# SparkFun_Amplified-Mic.net
KiCad netlist of a schematic drawn in EAGLE
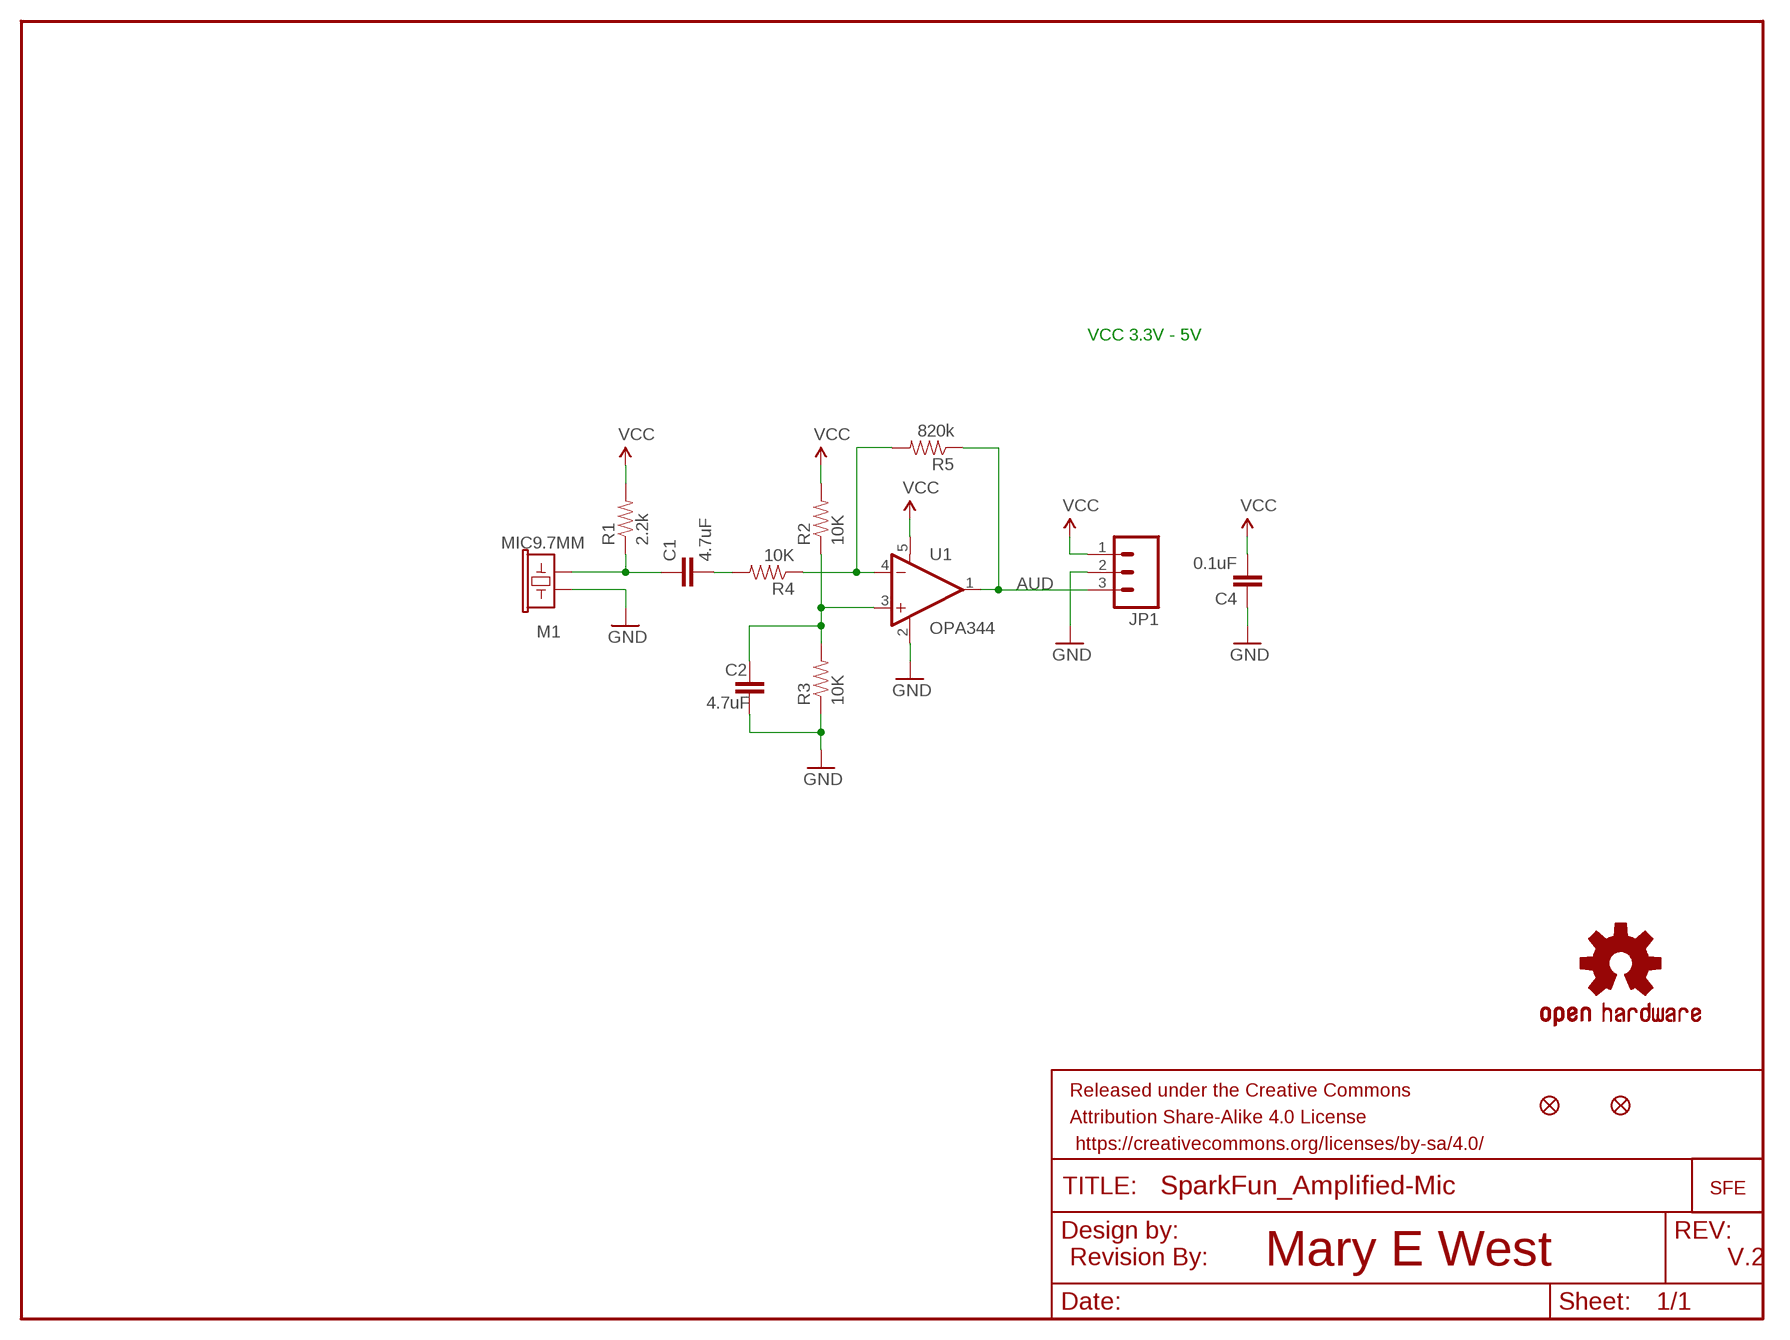
[diagram p0: schematic, sheet 1]

(export (version "E")
  (design (tool "Eeschema 10.0.6"))
  (components
    (comp (ref "C1")
      (value "4.7uF")
      (footprint "eagle-import:0603-CAP")
      (libsource (lib "eagle-import") (part "4.7UF-6.3V-10%(0603)0603"))
    )
    (comp (ref "C2")
      (value "4.7uF")
      (footprint "eagle-import:0603-CAP")
      (libsource (lib "eagle-import") (part "4.7UF-6.3V-10%(0603)0603"))
    )
    (comp (ref "C4")
      (value "0.1uF")
      (footprint "eagle-import:0603-CAP")
      (libsource (lib "eagle-import") (part "0.1UF-25V(+80/-20%)(0603)"))
    )
    (comp (ref "FRAME1")
      (value "FRAME-LETTER")
      (footprint "eagle-import:CREATIVE_COMMONS")
      (libsource (lib "eagle-import") (part "FRAME-LETTER"))
    )
    (comp (ref "JP1")
      (value "M03PTH")
      (footprint "eagle-import:1X03")
      (libsource (lib "eagle-import") (part "M03PTH"))
    )
    (comp (ref "JP2")
      (value "FIDUCIALUFIDUCIAL")
      (footprint "eagle-import:MICRO-FIDUCIAL")
      (libsource (lib "eagle-import") (part "FIDUCIALUFIDUCIAL"))
    )
    (comp (ref "JP3")
      (value "FIDUCIALUFIDUCIAL")
      (footprint "eagle-import:MICRO-FIDUCIAL")
      (libsource (lib "eagle-import") (part "FIDUCIALUFIDUCIAL"))
    )
    (comp (ref "LOGO1")
      (value "OSHW-LOGOMINI")
      (footprint "eagle-import:OSHW-LOGO-MINI")
      (libsource (lib "eagle-import") (part "OSHW-LOGOMINI"))
    )
    (comp (ref "M1")
      (value "MIC9.7MM")
      (footprint "eagle-import:MIC-9.7MM")
      (libsource (lib "eagle-import") (part "MIC9.7MM"))
    )
    (comp (ref "R1")
      (value "2.2k")
      (footprint "eagle-import:0603-RES")
      (libsource (lib "eagle-import") (part "2.2KOHM-1/10W-1%(0603)"))
    )
    (comp (ref "R2")
      (value "10K")
      (footprint "eagle-import:0603-RES")
      (libsource (lib "eagle-import") (part "10KOHM-1/10W-1%(0603)0603"))
    )
    (comp (ref "R3")
      (value "10K")
      (footprint "eagle-import:0603-RES")
      (libsource (lib "eagle-import") (part "10KOHM-1/10W-1%(0603)0603"))
    )
    (comp (ref "R4")
      (value "10K")
      (footprint "eagle-import:0603-RES")
      (libsource (lib "eagle-import") (part "10KOHM-1/10W-1%(0603)0603"))
    )
    (comp (ref "R5")
      (value "820k")
      (footprint "eagle-import:0603-RES")
      (libsource (lib "eagle-import") (part "820KOHM-1/10W-1%(0603)"))
    )
    (comp (ref "U$1")
      (value "LOGO-SFESK")
      (footprint "eagle-import:SFE-LOGO-FLAME")
      (libsource (lib "eagle-import") (part "LOGO-SFESK"))
    )
    (comp (ref "U$2")
      (value "REVISION")
      (footprint "eagle-import:REVISION")
      (libsource (lib "eagle-import") (part "REVISION"))
    )
    (comp (ref "U1")
      (value "OPA344")
      (footprint "eagle-import:SOT23-5")
      (libsource (lib "eagle-import") (part "OPA344"))
    )
  )
  (nets
    (net (code "1") (name "/AUD") (class "Default")
      (node (ref "JP1") (pin "3") (pinfunction "3_3") (pintype "passive"))
      (node (ref "R5") (pin "1") (pinfunction "1_1") (pintype "passive"))
      (node (ref "U1") (pin "1") (pinfunction "OUT_1") (pintype "output"))
    )
    (net (code "2") (name "GND") (class "Default")
      (node (ref "C2") (pin "2") (pinfunction "2_2") (pintype "passive"))
      (node (ref "C4") (pin "1") (pinfunction "1_1") (pintype "passive"))
      (node (ref "JP1") (pin "2") (pinfunction "2_2") (pintype "passive"))
      (node (ref "M1") (pin "2") (pinfunction "2_2") (pintype "passive"))
      (node (ref "R3") (pin "1") (pinfunction "1_1") (pintype "passive"))
      (node (ref "U1") (pin "2") (pinfunction "V-_2") (pintype "power_in"))
    )
    (net (code "3") (name "Net-(C1-Pad1)") (class "Default")
      (node (ref "C1") (pin "1") (pinfunction "1_1") (pintype "passive"))
      (node (ref "M1") (pin "1") (pinfunction "1_1") (pintype "passive"))
      (node (ref "R1") (pin "1") (pinfunction "1_1") (pintype "passive"))
    )
    (net (code "4") (name "Net-(C1-Pad2)") (class "Default")
      (node (ref "C1") (pin "2") (pinfunction "2_2") (pintype "passive"))
      (node (ref "R4") (pin "2") (pinfunction "2_2") (pintype "passive"))
    )
    (net (code "5") (name "Net-(U1-+IN)") (class "Default")
      (node (ref "C2") (pin "1") (pinfunction "1_1") (pintype "passive"))
      (node (ref "R2") (pin "1") (pinfunction "1_1") (pintype "passive"))
      (node (ref "R3") (pin "2") (pinfunction "2_2") (pintype "passive"))
      (node (ref "U1") (pin "3") (pinfunction "+IN_3") (pintype "input"))
    )
    (net (code "6") (name "Net-(U1--IN)") (class "Default")
      (node (ref "R4") (pin "1") (pinfunction "1_1") (pintype "passive"))
      (node (ref "R5") (pin "2") (pinfunction "2_2") (pintype "passive"))
      (node (ref "U1") (pin "4") (pinfunction "-IN_4") (pintype "input"))
    )
    (net (code "7") (name "VCC") (class "Default")
      (node (ref "C4") (pin "2") (pinfunction "2_2") (pintype "passive"))
      (node (ref "JP1") (pin "1") (pinfunction "1_1") (pintype "passive"))
      (node (ref "R1") (pin "2") (pinfunction "2_2") (pintype "passive"))
      (node (ref "R2") (pin "2") (pinfunction "2_2") (pintype "passive"))
      (node (ref "U1") (pin "5") (pinfunction "V+_5") (pintype "power_in"))
    )
  )
)
